# Sheet2.net
KiCad netlist of a schematic drawn in Altium Designer
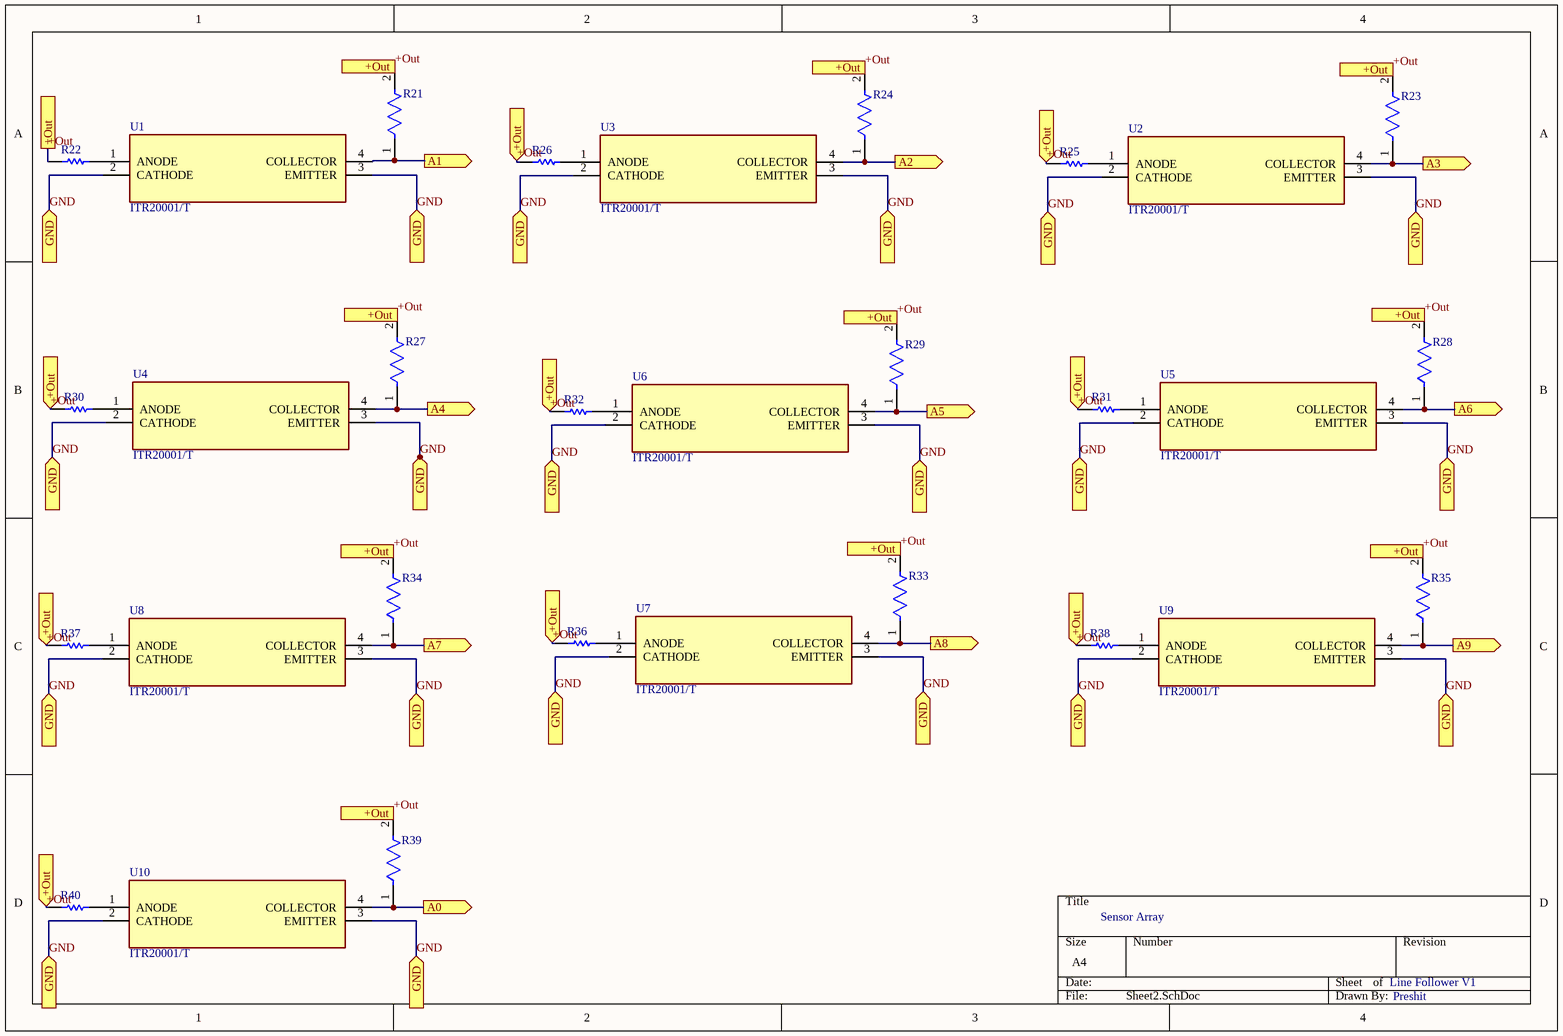
[diagram p0: Sheet2.SchDoc]

(export (version "E")
  (design (tool "Eeschema 10.0.6"))
  (components
    (comp (ref "R21")
      (value "RN732BTTDK1002B10")
      (footprint "FP-RN732B-MFG")
      (description "10kΩ ±0.1% 0.125W, 1/8W Chip Resistor 1206 (3216 Metric) Moisture Resistant Thin Film")
      (fields (field (name "TOLERANCE") "0.1%"))
      (libsource (lib "Altium Content Vault") (part "1029c3af85768c4190bb7ad29bc67b5"))
    )
    (comp (ref "R22")
      (value "220R 1% 2512(6432)")
      (footprint "RESC2512(6432)_L")
      (description "220R 1W 1% 2512 (6432 Metric)  SMD")
      (fields (field (name "POWER") "1 W") (field (name "TOLERANCE") "1 %"))
      (libsource (lib "Altium Content Vault") (part "RES"))
    )
    (comp (ref "R23")
      (value "RN732BTTDK1002B10")
      (footprint "FP-RN732B-MFG")
      (description "10kΩ ±0.1% 0.125W, 1/8W Chip Resistor 1206 (3216 Metric) Moisture Resistant Thin Film")
      (fields (field (name "TOLERANCE") "0.1%"))
      (libsource (lib "Altium Content Vault") (part "1029c3af85768c4190bb7ad29bc67b5"))
    )
    (comp (ref "R24")
      (value "RN732BTTDK1002B10")
      (footprint "FP-RN732B-MFG")
      (description "10kΩ ±0.1% 0.125W, 1/8W Chip Resistor 1206 (3216 Metric) Moisture Resistant Thin Film")
      (fields (field (name "TOLERANCE") "0.1%"))
      (libsource (lib "Altium Content Vault") (part "1029c3af85768c4190bb7ad29bc67b5"))
    )
    (comp (ref "R25")
      (value "220R 1% 2512(6432)")
      (footprint "RESC2512(6432)_L")
      (description "220R 1W 1% 2512 (6432 Metric)  SMD")
      (fields (field (name "POWER") "1 W") (field (name "TOLERANCE") "1 %"))
      (libsource (lib "Altium Content Vault") (part "RES"))
    )
    (comp (ref "R26")
      (value "220R 1% 2512(6432)")
      (footprint "RESC2512(6432)_L")
      (description "220R 1W 1% 2512 (6432 Metric)  SMD")
      (fields (field (name "POWER") "1 W") (field (name "TOLERANCE") "1 %"))
      (libsource (lib "Altium Content Vault") (part "RES"))
    )
    (comp (ref "R27")
      (value "RN732BTTDK1002B10")
      (footprint "FP-RN732B-MFG")
      (description "10kΩ ±0.1% 0.125W, 1/8W Chip Resistor 1206 (3216 Metric) Moisture Resistant Thin Film")
      (fields (field (name "TOLERANCE") "0.1%"))
      (libsource (lib "Altium Content Vault") (part "1029c3af85768c4190bb7ad29bc67b5"))
    )
    (comp (ref "R28")
      (value "RN732BTTDK1002B10")
      (footprint "FP-RN732B-MFG")
      (description "10kΩ ±0.1% 0.125W, 1/8W Chip Resistor 1206 (3216 Metric) Moisture Resistant Thin Film")
      (fields (field (name "TOLERANCE") "0.1%"))
      (libsource (lib "Altium Content Vault") (part "1029c3af85768c4190bb7ad29bc67b5"))
    )
    (comp (ref "R29")
      (value "RN732BTTDK1002B10")
      (footprint "FP-RN732B-MFG")
      (description "10kΩ ±0.1% 0.125W, 1/8W Chip Resistor 1206 (3216 Metric) Moisture Resistant Thin Film")
      (fields (field (name "TOLERANCE") "0.1%"))
      (libsource (lib "Altium Content Vault") (part "1029c3af85768c4190bb7ad29bc67b5"))
    )
    (comp (ref "R30")
      (value "220R 1% 2512(6432)")
      (footprint "RESC2512(6432)_L")
      (description "220R 1W 1% 2512 (6432 Metric)  SMD")
      (fields (field (name "POWER") "1 W") (field (name "TOLERANCE") "1 %"))
      (libsource (lib "Altium Content Vault") (part "RES"))
    )
    (comp (ref "R31")
      (value "220R 1% 2512(6432)")
      (footprint "RESC2512(6432)_L")
      (description "220R 1W 1% 2512 (6432 Metric)  SMD")
      (fields (field (name "POWER") "1 W") (field (name "TOLERANCE") "1 %"))
      (libsource (lib "Altium Content Vault") (part "RES"))
    )
    (comp (ref "R32")
      (value "220R 1% 2512(6432)")
      (footprint "RESC2512(6432)_L")
      (description "220R 1W 1% 2512 (6432 Metric)  SMD")
      (fields (field (name "POWER") "1 W") (field (name "TOLERANCE") "1 %"))
      (libsource (lib "Altium Content Vault") (part "RES"))
    )
    (comp (ref "R33")
      (value "RN732BTTDK1002B10")
      (footprint "FP-RN732B-MFG")
      (description "10kΩ ±0.1% 0.125W, 1/8W Chip Resistor 1206 (3216 Metric) Moisture Resistant Thin Film")
      (fields (field (name "TOLERANCE") "0.1%"))
      (libsource (lib "Altium Content Vault") (part "1029c3af85768c4190bb7ad29bc67b5"))
    )
    (comp (ref "R34")
      (value "RN732BTTDK1002B10")
      (footprint "FP-RN732B-MFG")
      (description "10kΩ ±0.1% 0.125W, 1/8W Chip Resistor 1206 (3216 Metric) Moisture Resistant Thin Film")
      (fields (field (name "TOLERANCE") "0.1%"))
      (libsource (lib "Altium Content Vault") (part "1029c3af85768c4190bb7ad29bc67b5"))
    )
    (comp (ref "R35")
      (value "RN732BTTDK1002B10")
      (footprint "FP-RN732B-MFG")
      (description "10kΩ ±0.1% 0.125W, 1/8W Chip Resistor 1206 (3216 Metric) Moisture Resistant Thin Film")
      (fields (field (name "TOLERANCE") "0.1%"))
      (libsource (lib "Altium Content Vault") (part "1029c3af85768c4190bb7ad29bc67b5"))
    )
    (comp (ref "R36")
      (value "220R 1% 2512(6432)")
      (footprint "RESC2512(6432)_L")
      (description "220R 1W 1% 2512 (6432 Metric)  SMD")
      (fields (field (name "POWER") "1 W") (field (name "TOLERANCE") "1 %"))
      (libsource (lib "Altium Content Vault") (part "RES"))
    )
    (comp (ref "R37")
      (value "220R 1% 2512(6432)")
      (footprint "RESC2512(6432)_L")
      (description "220R 1W 1% 2512 (6432 Metric)  SMD")
      (fields (field (name "POWER") "1 W") (field (name "TOLERANCE") "1 %"))
      (libsource (lib "Altium Content Vault") (part "RES"))
    )
    (comp (ref "R38")
      (value "220R 1% 2512(6432)")
      (footprint "RESC2512(6432)_L")
      (description "220R 1W 1% 2512 (6432 Metric)  SMD")
      (fields (field (name "POWER") "1 W") (field (name "TOLERANCE") "1 %"))
      (libsource (lib "Altium Content Vault") (part "RES"))
    )
    (comp (ref "R39")
      (value "RN732BTTDK1002B10")
      (footprint "FP-RN732B-MFG")
      (description "10kΩ ±0.1% 0.125W, 1/8W Chip Resistor 1206 (3216 Metric) Moisture Resistant Thin Film")
      (fields (field (name "TOLERANCE") "0.1%"))
      (libsource (lib "Altium Content Vault") (part "1029c3af85768c4190bb7ad29bc67b5"))
    )
    (comp (ref "R40")
      (value "220R 1% 2512(6432)")
      (footprint "RESC2512(6432)_L")
      (description "220R 1W 1% 2512 (6432 Metric)  SMD")
      (fields (field (name "POWER") "1 W") (field (name "TOLERANCE") "1 %"))
      (libsource (lib "Altium Content Vault") (part "RES"))
    )
    (comp (ref "U1")
      (value "ITR20001/T")
      (footprint "RELAY4_ITR20001/T_EVE")
      (description "Reflective Optical Sensor 0.197 (5mm) 4-DIP (0.100, 2.54mm)")
      (fields (field (name "MF") "Everlight Electronics"))
      (libsource (lib "Preshit Sapkale") (part "ITR20001/T"))
    )
    (comp (ref "U2")
      (value "ITR20001/T")
      (footprint "RELAY4_ITR20001/T_EVE")
      (description "Reflective Optical Sensor 0.197 (5mm) 4-DIP (0.100, 2.54mm)")
      (fields (field (name "MF") "Everlight Electronics"))
      (libsource (lib "Preshit Sapkale") (part "ITR20001/T"))
    )
    (comp (ref "U3")
      (value "ITR20001/T")
      (footprint "RELAY4_ITR20001/T_EVE")
      (description "Reflective Optical Sensor 0.197 (5mm) 4-DIP (0.100, 2.54mm)")
      (fields (field (name "MF") "Everlight Electronics"))
      (libsource (lib "Preshit Sapkale") (part "ITR20001/T"))
    )
    (comp (ref "U4")
      (value "ITR20001/T")
      (footprint "RELAY4_ITR20001/T_EVE")
      (description "Reflective Optical Sensor 0.197 (5mm) 4-DIP (0.100, 2.54mm)")
      (fields (field (name "MF") "Everlight Electronics"))
      (libsource (lib "Preshit Sapkale") (part "ITR20001/T"))
    )
    (comp (ref "U5")
      (value "ITR20001/T")
      (footprint "RELAY4_ITR20001/T_EVE")
      (description "Reflective Optical Sensor 0.197 (5mm) 4-DIP (0.100, 2.54mm)")
      (fields (field (name "MF") "Everlight Electronics"))
      (libsource (lib "Preshit Sapkale") (part "ITR20001/T"))
    )
    (comp (ref "U6")
      (value "ITR20001/T")
      (footprint "RELAY4_ITR20001/T_EVE")
      (description "Reflective Optical Sensor 0.197 (5mm) 4-DIP (0.100, 2.54mm)")
      (fields (field (name "MF") "Everlight Electronics"))
      (libsource (lib "Preshit Sapkale") (part "ITR20001/T"))
    )
    (comp (ref "U7")
      (value "ITR20001/T")
      (footprint "RELAY4_ITR20001/T_EVE")
      (description "Reflective Optical Sensor 0.197 (5mm) 4-DIP (0.100, 2.54mm)")
      (fields (field (name "MF") "Everlight Electronics"))
      (libsource (lib "Preshit Sapkale") (part "ITR20001/T"))
    )
    (comp (ref "U8")
      (value "ITR20001/T")
      (footprint "RELAY4_ITR20001/T_EVE")
      (description "Reflective Optical Sensor 0.197 (5mm) 4-DIP (0.100, 2.54mm)")
      (fields (field (name "MF") "Everlight Electronics"))
      (libsource (lib "Preshit Sapkale") (part "ITR20001/T"))
    )
    (comp (ref "U9")
      (value "ITR20001/T")
      (footprint "RELAY4_ITR20001/T_EVE")
      (description "Reflective Optical Sensor 0.197 (5mm) 4-DIP (0.100, 2.54mm)")
      (fields (field (name "MF") "Everlight Electronics"))
      (libsource (lib "Preshit Sapkale") (part "ITR20001/T"))
    )
    (comp (ref "U10")
      (value "ITR20001/T")
      (footprint "RELAY4_ITR20001/T_EVE")
      (description "Reflective Optical Sensor 0.197 (5mm) 4-DIP (0.100, 2.54mm)")
      (fields (field (name "MF") "Everlight Electronics"))
      (libsource (lib "Preshit Sapkale") (part "ITR20001/T"))
    )
  )
  (nets
    (net (code "1") (name "/+Out") (class "Default")
      (node (ref "R21") (pin "2") (pinfunction "2_2") (pintype "passive"))
      (node (ref "R22") (pin "1") (pinfunction "1_1") (pintype "passive"))
      (node (ref "R23") (pin "2") (pinfunction "2_2") (pintype "passive"))
      (node (ref "R24") (pin "2") (pinfunction "2_2") (pintype "passive"))
      (node (ref "R25") (pin "1") (pinfunction "1_1") (pintype "passive"))
      (node (ref "R26") (pin "1") (pinfunction "1_1") (pintype "passive"))
      (node (ref "R27") (pin "2") (pinfunction "2_2") (pintype "passive"))
      (node (ref "R28") (pin "2") (pinfunction "2_2") (pintype "passive"))
      (node (ref "R29") (pin "2") (pinfunction "2_2") (pintype "passive"))
      (node (ref "R30") (pin "1") (pinfunction "1_1") (pintype "passive"))
      (node (ref "R31") (pin "1") (pinfunction "1_1") (pintype "passive"))
      (node (ref "R32") (pin "1") (pinfunction "1_1") (pintype "passive"))
      (node (ref "R33") (pin "2") (pinfunction "2_2") (pintype "passive"))
      (node (ref "R34") (pin "2") (pinfunction "2_2") (pintype "passive"))
      (node (ref "R35") (pin "2") (pinfunction "2_2") (pintype "passive"))
      (node (ref "R36") (pin "1") (pinfunction "1_1") (pintype "passive"))
      (node (ref "R37") (pin "1") (pinfunction "1_1") (pintype "passive"))
      (node (ref "R38") (pin "1") (pinfunction "1_1") (pintype "passive"))
      (node (ref "R39") (pin "2") (pinfunction "2_2") (pintype "passive"))
      (node (ref "R40") (pin "1") (pinfunction "1_1") (pintype "passive"))
    )
    (net (code "2") (name "/A0") (class "Default")
      (node (ref "R39") (pin "1") (pinfunction "1_1") (pintype "passive"))
      (node (ref "U10") (pin "4") (pinfunction "COLLECTOR_4") (pintype "passive"))
    )
    (net (code "3") (name "/A1") (class "Default")
      (node (ref "R21") (pin "1") (pinfunction "1_1") (pintype "passive"))
      (node (ref "U1") (pin "4") (pinfunction "COLLECTOR_4") (pintype "passive"))
    )
    (net (code "4") (name "/A2") (class "Default")
      (node (ref "R24") (pin "1") (pinfunction "1_1") (pintype "passive"))
      (node (ref "U3") (pin "4") (pinfunction "COLLECTOR_4") (pintype "passive"))
    )
    (net (code "5") (name "/A3") (class "Default")
      (node (ref "R23") (pin "1") (pinfunction "1_1") (pintype "passive"))
      (node (ref "U2") (pin "4") (pinfunction "COLLECTOR_4") (pintype "passive"))
    )
    (net (code "6") (name "/A4") (class "Default")
      (node (ref "R27") (pin "1") (pinfunction "1_1") (pintype "passive"))
      (node (ref "U4") (pin "4") (pinfunction "COLLECTOR_4") (pintype "passive"))
    )
    (net (code "7") (name "/A5") (class "Default")
      (node (ref "R29") (pin "1") (pinfunction "1_1") (pintype "passive"))
      (node (ref "U6") (pin "4") (pinfunction "COLLECTOR_4") (pintype "passive"))
    )
    (net (code "8") (name "/A6") (class "Default")
      (node (ref "R28") (pin "1") (pinfunction "1_1") (pintype "passive"))
      (node (ref "U5") (pin "4") (pinfunction "COLLECTOR_4") (pintype "passive"))
    )
    (net (code "9") (name "/A7") (class "Default")
      (node (ref "R34") (pin "1") (pinfunction "1_1") (pintype "passive"))
      (node (ref "U8") (pin "4") (pinfunction "COLLECTOR_4") (pintype "passive"))
    )
    (net (code "10") (name "/A8") (class "Default")
      (node (ref "R33") (pin "1") (pinfunction "1_1") (pintype "passive"))
      (node (ref "U7") (pin "4") (pinfunction "COLLECTOR_4") (pintype "passive"))
    )
    (net (code "11") (name "/A9") (class "Default")
      (node (ref "R35") (pin "1") (pinfunction "1_1") (pintype "passive"))
      (node (ref "U9") (pin "4") (pinfunction "COLLECTOR_4") (pintype "passive"))
    )
    (net (code "12") (name "/GND") (class "Default")
      (node (ref "U1") (pin "2") (pinfunction "CATHODE_2") (pintype "passive"))
      (node (ref "U1") (pin "3") (pinfunction "EMITTER_3") (pintype "passive"))
      (node (ref "U10") (pin "2") (pinfunction "CATHODE_2") (pintype "passive"))
      (node (ref "U10") (pin "3") (pinfunction "EMITTER_3") (pintype "passive"))
      (node (ref "U2") (pin "2") (pinfunction "CATHODE_2") (pintype "passive"))
      (node (ref "U2") (pin "3") (pinfunction "EMITTER_3") (pintype "passive"))
      (node (ref "U3") (pin "2") (pinfunction "CATHODE_2") (pintype "passive"))
      (node (ref "U3") (pin "3") (pinfunction "EMITTER_3") (pintype "passive"))
      (node (ref "U4") (pin "2") (pinfunction "CATHODE_2") (pintype "passive"))
      (node (ref "U4") (pin "3") (pinfunction "EMITTER_3") (pintype "passive"))
      (node (ref "U5") (pin "2") (pinfunction "CATHODE_2") (pintype "passive"))
      (node (ref "U5") (pin "3") (pinfunction "EMITTER_3") (pintype "passive"))
      (node (ref "U6") (pin "2") (pinfunction "CATHODE_2") (pintype "passive"))
      (node (ref "U6") (pin "3") (pinfunction "EMITTER_3") (pintype "passive"))
      (node (ref "U7") (pin "2") (pinfunction "CATHODE_2") (pintype "passive"))
      (node (ref "U7") (pin "3") (pinfunction "EMITTER_3") (pintype "passive"))
      (node (ref "U8") (pin "2") (pinfunction "CATHODE_2") (pintype "passive"))
      (node (ref "U8") (pin "3") (pinfunction "EMITTER_3") (pintype "passive"))
      (node (ref "U9") (pin "2") (pinfunction "CATHODE_2") (pintype "passive"))
      (node (ref "U9") (pin "3") (pinfunction "EMITTER_3") (pintype "passive"))
    )
    (net (code "13") (name "Net-(U1-ANODE)") (class "Default")
      (node (ref "R22") (pin "2") (pinfunction "2_2") (pintype "passive"))
      (node (ref "U1") (pin "1") (pinfunction "ANODE_1") (pintype "passive"))
    )
    (net (code "14") (name "Net-(U2-ANODE)") (class "Default")
      (node (ref "R25") (pin "2") (pinfunction "2_2") (pintype "passive"))
      (node (ref "U2") (pin "1") (pinfunction "ANODE_1") (pintype "passive"))
    )
    (net (code "15") (name "Net-(U3-ANODE)") (class "Default")
      (node (ref "R26") (pin "2") (pinfunction "2_2") (pintype "passive"))
      (node (ref "U3") (pin "1") (pinfunction "ANODE_1") (pintype "passive"))
    )
    (net (code "16") (name "Net-(U4-ANODE)") (class "Default")
      (node (ref "R30") (pin "2") (pinfunction "2_2") (pintype "passive"))
      (node (ref "U4") (pin "1") (pinfunction "ANODE_1") (pintype "passive"))
    )
    (net (code "17") (name "Net-(U5-ANODE)") (class "Default")
      (node (ref "R31") (pin "2") (pinfunction "2_2") (pintype "passive"))
      (node (ref "U5") (pin "1") (pinfunction "ANODE_1") (pintype "passive"))
    )
    (net (code "18") (name "Net-(U6-ANODE)") (class "Default")
      (node (ref "R32") (pin "2") (pinfunction "2_2") (pintype "passive"))
      (node (ref "U6") (pin "1") (pinfunction "ANODE_1") (pintype "passive"))
    )
    (net (code "19") (name "Net-(U7-ANODE)") (class "Default")
      (node (ref "R36") (pin "2") (pinfunction "2_2") (pintype "passive"))
      (node (ref "U7") (pin "1") (pinfunction "ANODE_1") (pintype "passive"))
    )
    (net (code "20") (name "Net-(U8-ANODE)") (class "Default")
      (node (ref "R37") (pin "2") (pinfunction "2_2") (pintype "passive"))
      (node (ref "U8") (pin "1") (pinfunction "ANODE_1") (pintype "passive"))
    )
    (net (code "21") (name "Net-(U9-ANODE)") (class "Default")
      (node (ref "R38") (pin "2") (pinfunction "2_2") (pintype "passive"))
      (node (ref "U9") (pin "1") (pinfunction "ANODE_1") (pintype "passive"))
    )
    (net (code "22") (name "Net-(U10-ANODE)") (class "Default")
      (node (ref "R40") (pin "2") (pinfunction "2_2") (pintype "passive"))
      (node (ref "U10") (pin "1") (pinfunction "ANODE_1") (pintype "passive"))
    )
  )
)
